# IrrigationSystemShield.net
KiCad netlist of a schematic drawn in EAGLE
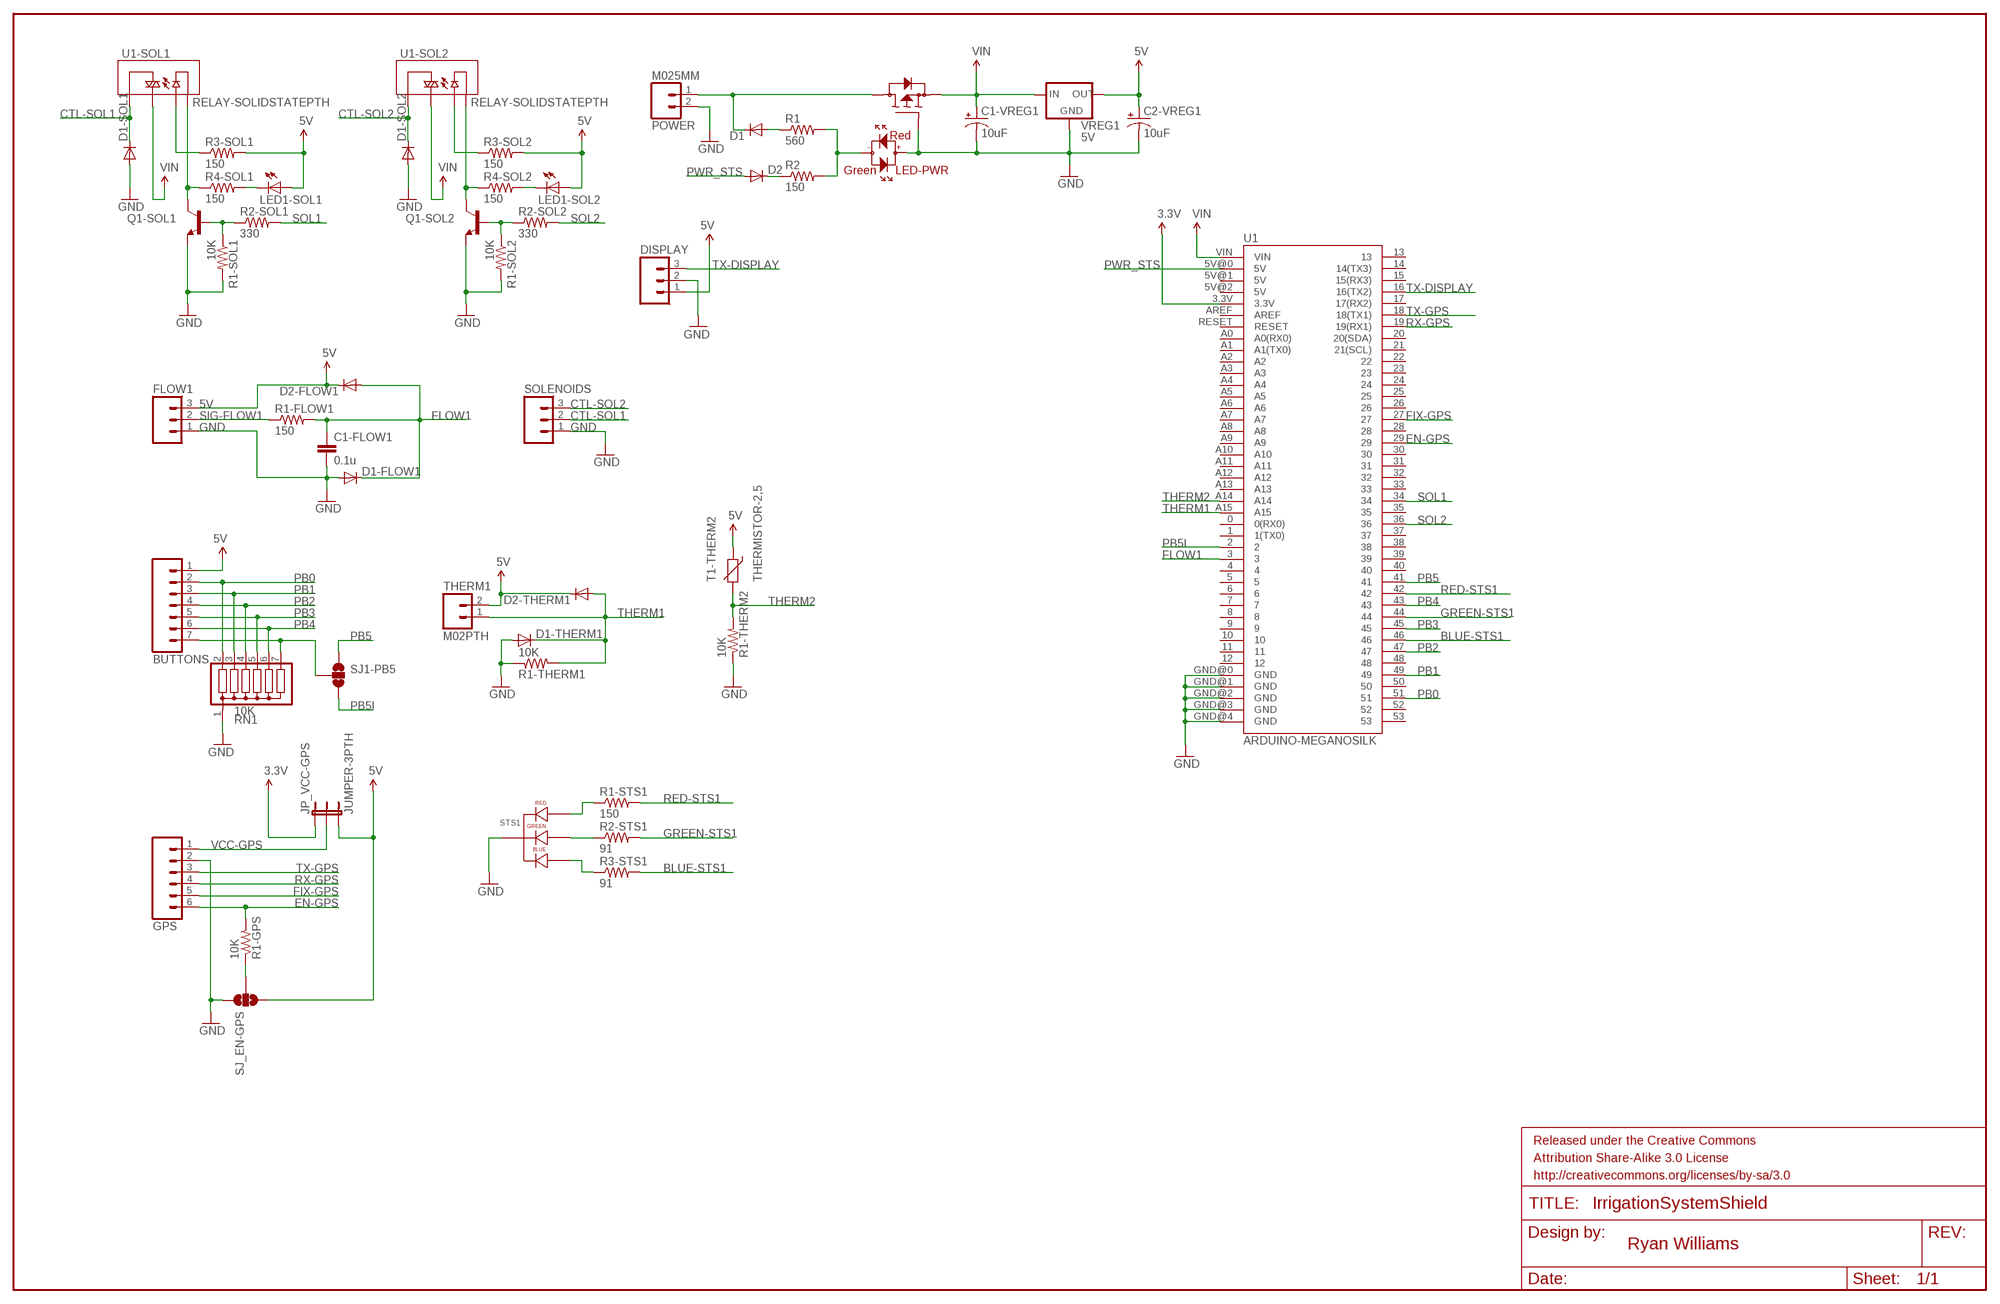
[diagram p0: schematic, sheet 1]

(export (version "E")
  (design (tool "Eeschema 10.0.6"))
  (components
    (comp (ref "BUTTONS")
      (value "M07")
      (footprint "eagle-import:1X07")
      (libsource (lib "eagle-import") (part "M07"))
    )
    (comp (ref "C1-FLOW1")
      (value "0.1u")
      (footprint "eagle-import:CAP-PTH-5MM")
      (libsource (lib "eagle-import") (part "CAPPTH1"))
    )
    (comp (ref "C1-VREG1")
      (value "10uF")
      (footprint "eagle-import:CPOL-RADIAL-10UF-25V")
      (libsource (lib "eagle-import") (part "10UF-25V-20%(PTH)"))
    )
    (comp (ref "C2-VREG1")
      (value "10uF")
      (footprint "eagle-import:CPOL-RADIAL-10UF-25V")
      (libsource (lib "eagle-import") (part "10UF-25V-20%(PTH)"))
    )
    (comp (ref "D1")
      (value "DIODEPTH")
      (footprint "eagle-import:DIODE-1N4001")
      (libsource (lib "eagle-import") (part "DIODEPTH"))
    )
    (comp (ref "D1-FLOW1")
      (value "DIODE1N4148")
      (footprint "eagle-import:DIODE-1N4148")
      (libsource (lib "eagle-import") (part "DIODE1N4148"))
    )
    (comp (ref "D1-SOL1")
      (value "DIODEPTH")
      (footprint "eagle-import:DIODE-1N4001")
      (libsource (lib "eagle-import") (part "DIODEPTH"))
    )
    (comp (ref "D1-SOL2")
      (value "DIODEPTH")
      (footprint "eagle-import:DIODE-1N4001")
      (libsource (lib "eagle-import") (part "DIODEPTH"))
    )
    (comp (ref "D1-THERM1")
      (value "DIODE1N4148")
      (footprint "eagle-import:DIODE-1N4148")
      (libsource (lib "eagle-import") (part "DIODE1N4148"))
    )
    (comp (ref "D2")
      (value "DIODEPTH")
      (footprint "eagle-import:DIODE-1N4001")
      (libsource (lib "eagle-import") (part "DIODEPTH"))
    )
    (comp (ref "D2-FLOW1")
      (value "DIODE1N4148")
      (footprint "eagle-import:DIODE-1N4148")
      (libsource (lib "eagle-import") (part "DIODE1N4148"))
    )
    (comp (ref "D2-THERM1")
      (value "DIODE1N4148")
      (footprint "eagle-import:DIODE-1N4148")
      (libsource (lib "eagle-import") (part "DIODE1N4148"))
    )
    (comp (ref "DISPLAY")
      (value "M03JST-PTH")
      (footprint "eagle-import:JST-3-PTH")
      (libsource (lib "eagle-import") (part "M03JST-PTH"))
    )
    (comp (ref "FET-1")
      (value "P-FET")
      (footprint "eagle-import:FQP27P06")
      (libsource (lib "eagle-import") (part "P-FET"))
    )
    (comp (ref "FLOW1")
      (value "M03-SCREW-5MM")
      (footprint "eagle-import:SCREWTERMINAL-5MM-3")
      (libsource (lib "eagle-import") (part "M03-SCREW-5MM"))
    )
    (comp (ref "FRAME1")
      (value "FRAME-LEDGER")
      (footprint "eagle-import:CREATIVE_COMMONS")
      (libsource (lib "eagle-import") (part "FRAME-LEDGER"))
    )
    (comp (ref "GPS")
      (value "M06SIP")
      (footprint "eagle-import:1X06")
      (libsource (lib "eagle-import") (part "M06SIP"))
    )
    (comp (ref "JP_VCC-GPS")
      (value "JUMPER-3PTH")
      (footprint "eagle-import:1X03")
      (libsource (lib "eagle-import") (part "JUMPER-3PTH"))
    )
    (comp (ref "LED-PWR")
      (value "LED-BIPOLARHGL*3362")
      (footprint "eagle-import:LED-5MM")
      (libsource (lib "eagle-import") (part "LED-BIPOLARL3362HG"))
    )
    (comp (ref "LED1-SOL1")
      (value "LED5MM")
      (footprint "eagle-import:LED5MM")
      (libsource (lib "eagle-import") (part "LED5MM"))
    )
    (comp (ref "LED1-SOL2")
      (value "LED5MM")
      (footprint "eagle-import:LED5MM")
      (libsource (lib "eagle-import") (part "LED5MM"))
    )
    (comp (ref "POWER")
      (value "M025MM")
      (footprint "eagle-import:SCREWTERMINAL-5MM-2")
      (libsource (lib "eagle-import") (part "M025MM"))
    )
    (comp (ref "Q1-SOL1")
      (value "TRANSISTOR_NPNTO92")
      (footprint "eagle-import:TO-92")
      (libsource (lib "eagle-import") (part "TRANSISTOR_NPNTO92"))
    )
    (comp (ref "Q1-SOL2")
      (value "TRANSISTOR_NPNTO92")
      (footprint "eagle-import:TO-92")
      (libsource (lib "eagle-import") (part "TRANSISTOR_NPNTO92"))
    )
    (comp (ref "R1")
      (value "560")
      (footprint "eagle-import:AXIAL-0.5")
      (libsource (lib "eagle-import") (part "RESISTORPTH-1/2W"))
    )
    (comp (ref "R1-FLOW1")
      (value "150")
      (footprint "eagle-import:AXIAL-0.4")
      (libsource (lib "eagle-import") (part "RESISTORPTH-1/4W"))
    )
    (comp (ref "R1-GPS")
      (value "10K")
      (footprint "eagle-import:AXIAL-0.4")
      (libsource (lib "eagle-import") (part "RESISTORPTH-1/4W"))
    )
    (comp (ref "R1-SOL1")
      (value "10K")
      (footprint "eagle-import:AXIAL-0.4")
      (libsource (lib "eagle-import") (part "RESISTORPTH-1/4W"))
    )
    (comp (ref "R1-SOL2")
      (value "10K")
      (footprint "eagle-import:AXIAL-0.4")
      (libsource (lib "eagle-import") (part "RESISTORPTH-1/4W"))
    )
    (comp (ref "R1-STS1")
      (value "150")
      (footprint "eagle-import:AXIAL-0.4")
      (libsource (lib "eagle-import") (part "RESISTORPTH-1/4W"))
    )
    (comp (ref "R1-THERM1")
      (value "10K")
      (footprint "eagle-import:AXIAL-0.4")
      (libsource (lib "eagle-import") (part "RESISTORPTH-1/4W"))
    )
    (comp (ref "R1-THERM2")
      (value "10K")
      (footprint "eagle-import:AXIAL-0.4")
      (libsource (lib "eagle-import") (part "RESISTORPTH-1/4W"))
    )
    (comp (ref "R2")
      (value "150")
      (footprint "eagle-import:AXIAL-0.4")
      (libsource (lib "eagle-import") (part "RESISTORPTH-1/4W"))
    )
    (comp (ref "R2-SOL1")
      (value "330")
      (footprint "eagle-import:AXIAL-0.4")
      (libsource (lib "eagle-import") (part "RESISTORPTH-1/4W"))
    )
    (comp (ref "R2-SOL2")
      (value "330")
      (footprint "eagle-import:AXIAL-0.4")
      (libsource (lib "eagle-import") (part "RESISTORPTH-1/4W"))
    )
    (comp (ref "R2-STS1")
      (value "91")
      (footprint "eagle-import:AXIAL-0.4")
      (libsource (lib "eagle-import") (part "RESISTORPTH-1/4W"))
    )
    (comp (ref "R3-SOL1")
      (value "150")
      (footprint "eagle-import:AXIAL-0.4")
      (libsource (lib "eagle-import") (part "RESISTORPTH-1/4W"))
    )
    (comp (ref "R3-SOL2")
      (value "150")
      (footprint "eagle-import:AXIAL-0.4")
      (libsource (lib "eagle-import") (part "RESISTORPTH-1/4W"))
    )
    (comp (ref "R3-STS1")
      (value "91")
      (footprint "eagle-import:AXIAL-0.4")
      (libsource (lib "eagle-import") (part "RESISTORPTH-1/4W"))
    )
    (comp (ref "R4-SOL1")
      (value "150")
      (footprint "eagle-import:AXIAL-0.4")
      (libsource (lib "eagle-import") (part "RESISTORPTH-1/4W"))
    )
    (comp (ref "R4-SOL2")
      (value "150")
      (footprint "eagle-import:AXIAL-0.4")
      (libsource (lib "eagle-import") (part "RESISTORPTH-1/4W"))
    )
    (comp (ref "RN1")
      (value "10K")
      (footprint "eagle-import:SIL7")
      (libsource (lib "eagle-import") (part "G06R"))
    )
    (comp (ref "SJ1-PB5")
      (value "SOLDERJUMPER_2WAYS")
      (footprint "eagle-import:SJ_3")
      (libsource (lib "eagle-import") (part "SOLDERJUMPER_2WAYS"))
    )
    (comp (ref "SJ_EN-GPS")
      (value "SOLDERJUMPER_2WAYS")
      (footprint "eagle-import:SJ_3")
      (libsource (lib "eagle-import") (part "SOLDERJUMPER_2WAYS"))
    )
    (comp (ref "SOLENOIDS")
      (value "M03-SCREW-5MM")
      (footprint "eagle-import:SCREWTERMINAL-5MM-3")
      (libsource (lib "eagle-import") (part "M03-SCREW-5MM"))
    )
    (comp (ref "STS1")
      (value "LED-RGB-CC-THRUDIFFUSE")
      (footprint "eagle-import:LED-RGB-THRU")
      (libsource (lib "eagle-import") (part "LED-RGB-CC-THRUDIFFUSE"))
    )
    (comp (ref "T1-THERM2")
      (value "THERMISTOR-2,5")
      (footprint "eagle-import:RS-2,5")
      (libsource (lib "eagle-import") (part "THERMISTOR-2,5"))
    )
    (comp (ref "THERM1")
      (value "M02PTH")
      (footprint "eagle-import:1X02")
      (libsource (lib "eagle-import") (part "M02PTH"))
    )
    (comp (ref "U1")
      (value "ARDUINO-MEGANOSILK")
      (footprint "eagle-import:ARDUINO_MEGA_NOSILK")
      (libsource (lib "eagle-import") (part "ARDUINO-MEGANOSILK"))
    )
    (comp (ref "U1-SOL1")
      (value "RELAY-SOLIDSTATEPTH")
      (footprint "eagle-import:RELAY-S108T02")
      (libsource (lib "eagle-import") (part "RELAY-SOLIDSTATEPTH"))
    )
    (comp (ref "U1-SOL2")
      (value "RELAY-SOLIDSTATEPTH")
      (footprint "eagle-import:RELAY-S108T02")
      (libsource (lib "eagle-import") (part "RELAY-SOLIDSTATEPTH"))
    )
    (comp (ref "VREG1")
      (value "5V")
      (footprint "eagle-import:TO220-IGO")
      (libsource (lib "eagle-import") (part "V_REG_78XXSINK"))
    )
  )
  (nets
    (net (code "1") (name "/BLUE-STS1") (class "Default")
      (node (ref "R3-STS1") (pin "P$2") (pinfunction "2_P$2") (pintype "passive"))
      (node (ref "U1") (pin "46") (pinfunction "46_46") (pintype "bidirectional"))
    )
    (net (code "2") (name "/CTL-SOL1") (class "Default")
      (node (ref "D1-SOL1") (pin "C") (pinfunction "C_C") (pintype "passive"))
      (node (ref "SOLENOIDS") (pin "2") (pinfunction "2_2") (pintype "passive"))
      (node (ref "U1-SOL1") (pin "1") (pinfunction "T1_1") (pintype "bidirectional"))
    )
    (net (code "3") (name "/CTL-SOL2") (class "Default")
      (node (ref "D1-SOL2") (pin "C") (pinfunction "C_C") (pintype "passive"))
      (node (ref "SOLENOIDS") (pin "3") (pinfunction "3_3") (pintype "passive"))
      (node (ref "U1-SOL2") (pin "1") (pinfunction "T1_1") (pintype "bidirectional"))
    )
    (net (code "4") (name "/EN-GPS") (class "Default")
      (node (ref "GPS") (pin "6") (pinfunction "6_6") (pintype "passive"))
      (node (ref "R1-GPS") (pin "P$2") (pinfunction "2_P$2") (pintype "passive"))
      (node (ref "U1") (pin "29") (pinfunction "29_29") (pintype "bidirectional"))
    )
    (net (code "5") (name "/FIX-GPS") (class "Default")
      (node (ref "GPS") (pin "5") (pinfunction "5_5") (pintype "passive"))
      (node (ref "U1") (pin "27") (pinfunction "27_27") (pintype "bidirectional"))
    )
    (net (code "6") (name "/FLOW1") (class "Default")
      (node (ref "C1-FLOW1") (pin "1") (pinfunction "1_1") (pintype "passive"))
      (node (ref "D1-FLOW1") (pin "C") (pinfunction "C_C") (pintype "passive"))
      (node (ref "D2-FLOW1") (pin "A") (pinfunction "A_A") (pintype "passive"))
      (node (ref "R1-FLOW1") (pin "P$2") (pinfunction "2_P$2") (pintype "passive"))
      (node (ref "U1") (pin "3") (pinfunction "3_3") (pintype "bidirectional"))
    )
    (net (code "7") (name "/GREEN-STS1") (class "Default")
      (node (ref "R2-STS1") (pin "P$2") (pinfunction "2_P$2") (pintype "passive"))
      (node (ref "U1") (pin "44") (pinfunction "44_44") (pintype "bidirectional"))
    )
    (net (code "8") (name "/PB0") (class "Default")
      (node (ref "BUTTONS") (pin "2") (pinfunction "2_2") (pintype "passive"))
      (node (ref "RN1") (pin "2") (pinfunction "2_2") (pintype "passive"))
      (node (ref "U1") (pin "51") (pinfunction "51_51") (pintype "bidirectional"))
    )
    (net (code "9") (name "/PB1") (class "Default")
      (node (ref "BUTTONS") (pin "3") (pinfunction "3_3") (pintype "passive"))
      (node (ref "RN1") (pin "3") (pinfunction "3_3") (pintype "passive"))
      (node (ref "U1") (pin "49") (pinfunction "49_49") (pintype "bidirectional"))
    )
    (net (code "10") (name "/PB2") (class "Default")
      (node (ref "BUTTONS") (pin "4") (pinfunction "4_4") (pintype "passive"))
      (node (ref "RN1") (pin "4") (pinfunction "4_4") (pintype "passive"))
      (node (ref "U1") (pin "47") (pinfunction "47_47") (pintype "bidirectional"))
    )
    (net (code "11") (name "/PB3") (class "Default")
      (node (ref "BUTTONS") (pin "5") (pinfunction "5_5") (pintype "passive"))
      (node (ref "RN1") (pin "5") (pinfunction "5_5") (pintype "passive"))
      (node (ref "U1") (pin "45") (pinfunction "45_45") (pintype "bidirectional"))
    )
    (net (code "12") (name "/PB4") (class "Default")
      (node (ref "BUTTONS") (pin "6") (pinfunction "6_6") (pintype "passive"))
      (node (ref "RN1") (pin "6") (pinfunction "6_6") (pintype "passive"))
      (node (ref "U1") (pin "43") (pinfunction "43_43") (pintype "bidirectional"))
    )
    (net (code "13") (name "/PB5") (class "Default")
      (node (ref "SJ1-PB5") (pin "1") (pinfunction "1_1") (pintype "passive"))
      (node (ref "U1") (pin "41") (pinfunction "41_41") (pintype "bidirectional"))
    )
    (net (code "14") (name "/PB5I") (class "Default")
      (node (ref "SJ1-PB5") (pin "3") (pinfunction "3_3") (pintype "passive"))
      (node (ref "U1") (pin "2") (pinfunction "2_2") (pintype "bidirectional"))
    )
    (net (code "15") (name "/PWR_STS") (class "Default")
      (node (ref "D2") (pin "A") (pinfunction "A_A") (pintype "passive"))
      (node (ref "U1") (pin "5V@0") (pinfunction "5V_5V@0") (pintype "bidirectional"))
    )
    (net (code "16") (name "/RED-STS1") (class "Default")
      (node (ref "R1-STS1") (pin "P$2") (pinfunction "2_P$2") (pintype "passive"))
      (node (ref "U1") (pin "42") (pinfunction "42_42") (pintype "bidirectional"))
    )
    (net (code "17") (name "/RX-GPS") (class "Default")
      (node (ref "GPS") (pin "4") (pinfunction "4_4") (pintype "passive"))
      (node (ref "U1") (pin "19") (pinfunction "19(RX1)_19") (pintype "bidirectional"))
    )
    (net (code "18") (name "/SIG-FLOW1") (class "Default")
      (node (ref "FLOW1") (pin "2") (pinfunction "2_2") (pintype "passive"))
      (node (ref "R1-FLOW1") (pin "P$1") (pinfunction "1_P$1") (pintype "passive"))
    )
    (net (code "19") (name "/SOL1") (class "Default")
      (node (ref "R2-SOL1") (pin "P$2") (pinfunction "2_P$2") (pintype "passive"))
      (node (ref "U1") (pin "34") (pinfunction "34_34") (pintype "bidirectional"))
    )
    (net (code "20") (name "/SOL2") (class "Default")
      (node (ref "R2-SOL2") (pin "P$2") (pinfunction "2_P$2") (pintype "passive"))
      (node (ref "U1") (pin "36") (pinfunction "36_36") (pintype "bidirectional"))
    )
    (net (code "21") (name "/THERM1") (class "Default")
      (node (ref "D1-THERM1") (pin "C") (pinfunction "C_C") (pintype "passive"))
      (node (ref "D2-THERM1") (pin "A") (pinfunction "A_A") (pintype "passive"))
      (node (ref "R1-THERM1") (pin "P$2") (pinfunction "2_P$2") (pintype "passive"))
      (node (ref "THERM1") (pin "1") (pinfunction "1_1") (pintype "passive"))
      (node (ref "U1") (pin "A15") (pinfunction "A15_A15") (pintype "bidirectional"))
    )
    (net (code "22") (name "/THERM2") (class "Default")
      (node (ref "R1-THERM2") (pin "P$2") (pinfunction "2_P$2") (pintype "passive"))
      (node (ref "T1-THERM2") (pin "2") (pinfunction "2_2") (pintype "passive"))
      (node (ref "U1") (pin "A14") (pinfunction "A14_A14") (pintype "bidirectional"))
    )
    (net (code "23") (name "/TX-DISPLAY") (class "Default")
      (node (ref "DISPLAY") (pin "3") (pinfunction "3_3") (pintype "passive"))
      (node (ref "U1") (pin "16") (pinfunction "16(TX2)_16") (pintype "bidirectional"))
    )
    (net (code "24") (name "/TX-GPS") (class "Default")
      (node (ref "GPS") (pin "3") (pinfunction "3_3") (pintype "passive"))
      (node (ref "U1") (pin "18") (pinfunction "18(TX1)_18") (pintype "bidirectional"))
    )
    (net (code "25") (name "/VCC-GPS") (class "Default")
      (node (ref "GPS") (pin "1") (pinfunction "1_1") (pintype "passive"))
      (node (ref "JP_VCC-GPS") (pin "2") (pinfunction "2_2") (pintype "passive"))
    )
    (net (code "26") (name "3.3V") (class "Default")
      (node (ref "JP_VCC-GPS") (pin "1") (pinfunction "1_1") (pintype "passive"))
      (node (ref "U1") (pin "3.3V") (pinfunction "3.3V_3.3V") (pintype "bidirectional"))
    )
    (net (code "27") (name "5V") (class "Default")
      (node (ref "BUTTONS") (pin "1") (pinfunction "1_1") (pintype "passive"))
      (node (ref "C2-VREG1") (pin "1") (pinfunction "+_1") (pintype "passive"))
      (node (ref "D2-FLOW1") (pin "C") (pinfunction "C_C") (pintype "passive"))
      (node (ref "D2-THERM1") (pin "C") (pinfunction "C_C") (pintype "passive"))
      (node (ref "DISPLAY") (pin "1") (pinfunction "1_1") (pintype "passive"))
      (node (ref "FLOW1") (pin "3") (pinfunction "3_3") (pintype "passive"))
      (node (ref "JP_VCC-GPS") (pin "3") (pinfunction "3_3") (pintype "passive"))
      (node (ref "LED1-SOL1") (pin "A") (pinfunction "A_A") (pintype "passive"))
      (node (ref "LED1-SOL2") (pin "A") (pinfunction "A_A") (pintype "passive"))
      (node (ref "R3-SOL1") (pin "P$2") (pinfunction "2_P$2") (pintype "passive"))
      (node (ref "R3-SOL2") (pin "P$2") (pinfunction "2_P$2") (pintype "passive"))
      (node (ref "SJ_EN-GPS") (pin "3") (pinfunction "3_3") (pintype "passive"))
      (node (ref "T1-THERM2") (pin "1") (pinfunction "1_1") (pintype "passive"))
      (node (ref "THERM1") (pin "2") (pinfunction "2_2") (pintype "passive"))
      (node (ref "VREG1") (pin "OUT") (pinfunction "OUT_OUT") (pintype "output"))
    )
    (net (code "28") (name "GND") (class "Default")
      (node (ref "C1-FLOW1") (pin "2") (pinfunction "2_2") (pintype "passive"))
      (node (ref "C1-VREG1") (pin "2") (pinfunction "-_2") (pintype "passive"))
      (node (ref "C2-VREG1") (pin "2") (pinfunction "-_2") (pintype "passive"))
      (node (ref "D1-FLOW1") (pin "A") (pinfunction "A_A") (pintype "passive"))
      (node (ref "D1-SOL1") (pin "A") (pinfunction "A_A") (pintype "passive"))
      (node (ref "D1-SOL2") (pin "A") (pinfunction "A_A") (pintype "passive"))
      (node (ref "D1-THERM1") (pin "A") (pinfunction "A_A") (pintype "passive"))
      (node (ref "DISPLAY") (pin "2") (pinfunction "2_2") (pintype "passive"))
      (node (ref "FET-1") (pin "GATE") (pinfunction "GATE_GATE") (pintype "bidirectional"))
      (node (ref "FLOW1") (pin "1") (pinfunction "1_1") (pintype "passive"))
      (node (ref "GPS") (pin "2") (pinfunction "2_2") (pintype "passive"))
      (node (ref "LED-PWR") (pin "ANODE") (pinfunction "ANODE_ANODE") (pintype "bidirectional"))
      (node (ref "POWER") (pin "2") (pinfunction "2_2") (pintype "passive"))
      (node (ref "Q1-SOL1") (pin "1") (pinfunction "E_1") (pintype "passive"))
      (node (ref "Q1-SOL2") (pin "1") (pinfunction "E_1") (pintype "passive"))
      (node (ref "R1-SOL1") (pin "P$2") (pinfunction "2_P$2") (pintype "passive"))
      (node (ref "R1-SOL2") (pin "P$2") (pinfunction "2_P$2") (pintype "passive"))
      (node (ref "R1-THERM1") (pin "P$1") (pinfunction "1_P$1") (pintype "passive"))
      (node (ref "R1-THERM2") (pin "P$1") (pinfunction "1_P$1") (pintype "passive"))
      (node (ref "RN1") (pin "1") (pinfunction "1_1") (pintype "passive"))
      (node (ref "SJ_EN-GPS") (pin "1") (pinfunction "1_1") (pintype "passive"))
      (node (ref "SOLENOIDS") (pin "1") (pinfunction "1_1") (pintype "passive"))
      (node (ref "STS1") (pin "2") (pinfunction "CATHODE_2") (pintype "bidirectional"))
      (node (ref "U1") (pin "GND@0") (pinfunction "GND_GND@0") (pintype "bidirectional"))
      (node (ref "U1") (pin "GND@1") (pinfunction "GND_GND@1") (pintype "bidirectional"))
      (node (ref "U1") (pin "GND@2") (pinfunction "GND_GND@2") (pintype "bidirectional"))
      (node (ref "U1") (pin "GND@3") (pinfunction "GND_GND@3") (pintype "bidirectional"))
      (node (ref "U1") (pin "GND@4") (pinfunction "GND_GND@4") (pintype "bidirectional"))
      (node (ref "VREG1") (pin "GND") (pinfunction "GND_GND") (pintype "input"))
    )
    (net (code "29") (name "Net-(BUTTONS-Pad7)") (class "Default")
      (node (ref "BUTTONS") (pin "7") (pinfunction "7_7") (pintype "passive"))
      (node (ref "RN1") (pin "7") (pinfunction "7_7") (pintype "passive"))
      (node (ref "SJ1-PB5") (pin "2") (pinfunction "2_2") (pintype "passive"))
    )
    (net (code "30") (name "Net-(D1-PadC)") (class "Default")
      (node (ref "D1") (pin "C") (pinfunction "C_C") (pintype "passive"))
      (node (ref "FET-1") (pin "DRAIN") (pinfunction "DRAIN_DRAIN") (pintype "bidirectional"))
      (node (ref "POWER") (pin "1") (pinfunction "1_1") (pintype "passive"))
    )
    (net (code "31") (name "Net-(LED1-SOL1-C)") (class "Default")
      (node (ref "LED1-SOL1") (pin "K") (pinfunction "C_K") (pintype "passive"))
      (node (ref "R4-SOL1") (pin "P$2") (pinfunction "2_P$2") (pintype "passive"))
    )
    (net (code "32") (name "Net-(LED1-SOL2-C)") (class "Default")
      (node (ref "LED1-SOL2") (pin "K") (pinfunction "C_K") (pintype "passive"))
      (node (ref "R4-SOL2") (pin "P$2") (pinfunction "2_P$2") (pintype "passive"))
    )
    (net (code "33") (name "Net-(Q1-SOL1-B)") (class "Default")
      (node (ref "Q1-SOL1") (pin "2") (pinfunction "B_2") (pintype "passive"))
      (node (ref "R1-SOL1") (pin "P$1") (pinfunction "1_P$1") (pintype "passive"))
      (node (ref "R2-SOL1") (pin "P$1") (pinfunction "1_P$1") (pintype "passive"))
    )
    (net (code "34") (name "Net-(Q1-SOL1-C)") (class "Default")
      (node (ref "Q1-SOL1") (pin "3") (pinfunction "C_3") (pintype "passive"))
      (node (ref "R4-SOL1") (pin "P$1") (pinfunction "1_P$1") (pintype "passive"))
      (node (ref "U1-SOL1") (pin "4") (pinfunction "-_4") (pintype "bidirectional"))
    )
    (net (code "35") (name "Net-(Q1-SOL2-B)") (class "Default")
      (node (ref "Q1-SOL2") (pin "2") (pinfunction "B_2") (pintype "passive"))
      (node (ref "R1-SOL2") (pin "P$1") (pinfunction "1_P$1") (pintype "passive"))
      (node (ref "R2-SOL2") (pin "P$1") (pinfunction "1_P$1") (pintype "passive"))
    )
    (net (code "36") (name "Net-(Q1-SOL2-C)") (class "Default")
      (node (ref "Q1-SOL2") (pin "3") (pinfunction "C_3") (pintype "passive"))
      (node (ref "R4-SOL2") (pin "P$1") (pinfunction "1_P$1") (pintype "passive"))
      (node (ref "U1-SOL2") (pin "4") (pinfunction "-_4") (pintype "bidirectional"))
    )
    (net (code "37") (name "Net-(R1-1)") (class "Default")
      (node (ref "D1") (pin "A") (pinfunction "A_A") (pintype "passive"))
      (node (ref "R1") (pin "P$1") (pinfunction "1_P$1") (pintype "passive"))
    )
    (net (code "38") (name "Net-(R1-2)") (class "Default")
      (node (ref "LED-PWR") (pin "CATHODE") (pinfunction "CATHODE_CATHODE") (pintype "bidirectional"))
      (node (ref "R1") (pin "P$2") (pinfunction "2_P$2") (pintype "passive"))
      (node (ref "R2") (pin "P$2") (pinfunction "2_P$2") (pintype "passive"))
    )
    (net (code "39") (name "Net-(R1-GPS-1)") (class "Default")
      (node (ref "R1-GPS") (pin "P$1") (pinfunction "1_P$1") (pintype "passive"))
      (node (ref "SJ_EN-GPS") (pin "2") (pinfunction "2_2") (pintype "passive"))
    )
    (net (code "40") (name "Net-(R1-STS1-1)") (class "Default")
      (node (ref "R1-STS1") (pin "P$1") (pinfunction "1_P$1") (pintype "passive"))
      (node (ref "STS1") (pin "1") (pinfunction "RED_CATHODE_1") (pintype "bidirectional"))
    )
    (net (code "41") (name "Net-(R2-1)") (class "Default")
      (node (ref "D2") (pin "C") (pinfunction "C_C") (pintype "passive"))
      (node (ref "R2") (pin "P$1") (pinfunction "1_P$1") (pintype "passive"))
    )
    (net (code "42") (name "Net-(R2-STS1-1)") (class "Default")
      (node (ref "R2-STS1") (pin "P$1") (pinfunction "1_P$1") (pintype "passive"))
      (node (ref "STS1") (pin "3") (pinfunction "GREEN_CATHODE_3") (pintype "bidirectional"))
    )
    (net (code "43") (name "Net-(R3-SOL1-1)") (class "Default")
      (node (ref "R3-SOL1") (pin "P$1") (pinfunction "1_P$1") (pintype "passive"))
      (node (ref "U1-SOL1") (pin "3") (pinfunction "+_3") (pintype "bidirectional"))
    )
    (net (code "44") (name "Net-(R3-SOL2-1)") (class "Default")
      (node (ref "R3-SOL2") (pin "P$1") (pinfunction "1_P$1") (pintype "passive"))
      (node (ref "U1-SOL2") (pin "3") (pinfunction "+_3") (pintype "bidirectional"))
    )
    (net (code "45") (name "Net-(R3-STS1-1)") (class "Default")
      (node (ref "R3-STS1") (pin "P$1") (pinfunction "1_P$1") (pintype "passive"))
      (node (ref "STS1") (pin "4") (pinfunction "BLUE_CATHODE_4") (pintype "bidirectional"))
    )
    (net (code "46") (name "VIN") (class "Default")
      (node (ref "C1-VREG1") (pin "1") (pinfunction "+_1") (pintype "passive"))
      (node (ref "FET-1") (pin "SOURCE") (pinfunction "SOURCE_SOURCE") (pintype "bidirectional"))
      (node (ref "U1") (pin "VIN") (pinfunction "VIN_VIN") (pintype "bidirectional"))
      (node (ref "U1-SOL1") (pin "2") (pinfunction "T2_2") (pintype "bidirectional"))
      (node (ref "U1-SOL2") (pin "2") (pinfunction "T2_2") (pintype "bidirectional"))
      (node (ref "VREG1") (pin "IN") (pinfunction "IN_IN") (pintype "input"))
    )
    (net (code "47") (name "unconnected-(U1-0(RX0)-Pad0)") (class "Default")
      (node (ref "U1") (pin "0") (pinfunction "0(RX0)_0") (pintype "bidirectional"))
    )
    (net (code "48") (name "unconnected-(U1-1(TX0)-Pad1)") (class "Default")
      (node (ref "U1") (pin "1") (pinfunction "1(TX0)_1") (pintype "bidirectional"))
    )
    (net (code "49") (name "unconnected-(U1-5V-Pad5V@1)") (class "Default")
      (node (ref "U1") (pin "5V@1") (pinfunction "5V_5V@1") (pintype "bidirectional"))
    )
    (net (code "50") (name "unconnected-(U1-5V-Pad5V@2)") (class "Default")
      (node (ref "U1") (pin "5V@2") (pinfunction "5V_5V@2") (pintype "bidirectional"))
    )
    (net (code "51") (name "unconnected-(U1-14(TX3)-Pad14)") (class "Default")
      (node (ref "U1") (pin "14") (pinfunction "14(TX3)_14") (pintype "bidirectional"))
    )
    (net (code "52") (name "unconnected-(U1-15(RX3)-Pad15)") (class "Default")
      (node (ref "U1") (pin "15") (pinfunction "15(RX3)_15") (pintype "bidirectional"))
    )
    (net (code "53") (name "unconnected-(U1-17(RX2)-Pad17)") (class "Default")
      (node (ref "U1") (pin "17") (pinfunction "17(RX2)_17") (pintype "bidirectional"))
    )
    (net (code "54") (name "unconnected-(U1-20(SDA)-Pad20)") (class "Default")
      (node (ref "U1") (pin "20") (pinfunction "20(SDA)_20") (pintype "bidirectional"))
    )
    (net (code "55") (name "unconnected-(U1-21(SCL)-Pad21)") (class "Default")
      (node (ref "U1") (pin "21") (pinfunction "21(SCL)_21") (pintype "bidirectional"))
    )
    (net (code "56") (name "unconnected-(U1-A0(RX0)-PadA0)") (class "Default")
      (node (ref "U1") (pin "A0") (pinfunction "A0(RX0)_A0") (pintype "bidirectional"))
    )
    (net (code "57") (name "unconnected-(U1-A1(TX0)-PadA1)") (class "Default")
      (node (ref "U1") (pin "A1") (pinfunction "A1(TX0)_A1") (pintype "bidirectional"))
    )
    (net (code "58") (name "unconnected-(U1-Pad4)") (class "Default")
      (node (ref "U1") (pin "4") (pinfunction "4_4") (pintype "bidirectional"))
    )
    (net (code "59") (name "unconnected-(U1-Pad5)") (class "Default")
      (node (ref "U1") (pin "5") (pinfunction "5_5") (pintype "bidirectional"))
    )
    (net (code "60") (name "unconnected-(U1-Pad6)") (class "Default")
      (node (ref "U1") (pin "6") (pinfunction "6_6") (pintype "bidirectional"))
    )
    (net (code "61") (name "unconnected-(U1-Pad7)") (class "Default")
      (node (ref "U1") (pin "7") (pinfunction "7_7") (pintype "bidirectional"))
    )
    (net (code "62") (name "unconnected-(U1-Pad8)") (class "Default")
      (node (ref "U1") (pin "8") (pinfunction "8_8") (pintype "bidirectional"))
    )
    (net (code "63") (name "unconnected-(U1-Pad9)") (class "Default")
      (node (ref "U1") (pin "9") (pinfunction "9_9") (pintype "bidirectional"))
    )
    (net (code "64") (name "unconnected-(U1-Pad10)") (class "Default")
      (node (ref "U1") (pin "10") (pinfunction "10_10") (pintype "bidirectional"))
    )
    (net (code "65") (name "unconnected-(U1-Pad11)") (class "Default")
      (node (ref "U1") (pin "11") (pinfunction "11_11") (pintype "bidirectional"))
    )
    (net (code "66") (name "unconnected-(U1-Pad12)") (class "Default")
      (node (ref "U1") (pin "12") (pinfunction "12_12") (pintype "bidirectional"))
    )
    (net (code "67") (name "unconnected-(U1-Pad13)") (class "Default")
      (node (ref "U1") (pin "13") (pinfunction "13_13") (pintype "bidirectional"))
    )
    (net (code "68") (name "unconnected-(U1-Pad22)") (class "Default")
      (node (ref "U1") (pin "22") (pinfunction "22_22") (pintype "bidirectional"))
    )
    (net (code "69") (name "unconnected-(U1-Pad23)") (class "Default")
      (node (ref "U1") (pin "23") (pinfunction "23_23") (pintype "bidirectional"))
    )
    (net (code "70") (name "unconnected-(U1-Pad24)") (class "Default")
      (node (ref "U1") (pin "24") (pinfunction "24_24") (pintype "bidirectional"))
    )
    (net (code "71") (name "unconnected-(U1-Pad25)") (class "Default")
      (node (ref "U1") (pin "25") (pinfunction "25_25") (pintype "bidirectional"))
    )
    (net (code "72") (name "unconnected-(U1-Pad26)") (class "Default")
      (node (ref "U1") (pin "26") (pinfunction "26_26") (pintype "bidirectional"))
    )
    (net (code "73") (name "unconnected-(U1-Pad28)") (class "Default")
      (node (ref "U1") (pin "28") (pinfunction "28_28") (pintype "bidirectional"))
    )
    (net (code "74") (name "unconnected-(U1-Pad30)") (class "Default")
      (node (ref "U1") (pin "30") (pinfunction "30_30") (pintype "bidirectional"))
    )
    (net (code "75") (name "unconnected-(U1-Pad31)") (class "Default")
      (node (ref "U1") (pin "31") (pinfunction "31_31") (pintype "bidirectional"))
    )
    (net (code "76") (name "unconnected-(U1-Pad32)") (class "Default")
      (node (ref "U1") (pin "32") (pinfunction "32_32") (pintype "bidirectional"))
    )
    (net (code "77") (name "unconnected-(U1-Pad33)") (class "Default")
      (node (ref "U1") (pin "33") (pinfunction "33_33") (pintype "bidirectional"))
    )
    (net (code "78") (name "unconnected-(U1-Pad35)") (class "Default")
      (node (ref "U1") (pin "35") (pinfunction "35_35") (pintype "bidirectional"))
    )
    (net (code "79") (name "unconnected-(U1-Pad37)") (class "Default")
      (node (ref "U1") (pin "37") (pinfunction "37_37") (pintype "bidirectional"))
    )
    (net (code "80") (name "unconnected-(U1-Pad38)") (class "Default")
      (node (ref "U1") (pin "38") (pinfunction "38_38") (pintype "bidirectional"))
    )
    (net (code "81") (name "unconnected-(U1-Pad39)") (class "Default")
      (node (ref "U1") (pin "39") (pinfunction "39_39") (pintype "bidirectional"))
    )
    (net (code "82") (name "unconnected-(U1-Pad40)") (class "Default")
      (node (ref "U1") (pin "40") (pinfunction "40_40") (pintype "bidirectional"))
    )
    (net (code "83") (name "unconnected-(U1-Pad48)") (class "Default")
      (node (ref "U1") (pin "48") (pinfunction "48_48") (pintype "bidirectional"))
    )
    (net (code "84") (name "unconnected-(U1-Pad50)") (class "Default")
      (node (ref "U1") (pin "50") (pinfunction "50_50") (pintype "bidirectional"))
    )
    (net (code "85") (name "unconnected-(U1-Pad52)") (class "Default")
      (node (ref "U1") (pin "52") (pinfunction "52_52") (pintype "bidirectional"))
    )
    (net (code "86") (name "unconnected-(U1-Pad53)") (class "Default")
      (node (ref "U1") (pin "53") (pinfunction "53_53") (pintype "bidirectional"))
    )
    (net (code "87") (name "unconnected-(U1-PadA2)") (class "Default")
      (node (ref "U1") (pin "A2") (pinfunction "A2_A2") (pintype "bidirectional"))
    )
    (net (code "88") (name "unconnected-(U1-PadA3)") (class "Default")
      (node (ref "U1") (pin "A3") (pinfunction "A3_A3") (pintype "bidirectional"))
    )
    (net (code "89") (name "unconnected-(U1-PadA4)") (class "Default")
      (node (ref "U1") (pin "A4") (pinfunction "A4_A4") (pintype "bidirectional"))
    )
    (net (code "90") (name "unconnected-(U1-PadA5)") (class "Default")
      (node (ref "U1") (pin "A5") (pinfunction "A5_A5") (pintype "bidirectional"))
    )
    (net (code "91") (name "unconnected-(U1-PadA6)") (class "Default")
      (node (ref "U1") (pin "A6") (pinfunction "A6_A6") (pintype "bidirectional"))
    )
    (net (code "92") (name "unconnected-(U1-PadA7)") (class "Default")
      (node (ref "U1") (pin "A7") (pinfunction "A7_A7") (pintype "bidirectional"))
    )
    (net (code "93") (name "unconnected-(U1-PadA8)") (class "Default")
      (node (ref "U1") (pin "A8") (pinfunction "A8_A8") (pintype "bidirectional"))
    )
    (net (code "94") (name "unconnected-(U1-PadA9)") (class "Default")
      (node (ref "U1") (pin "A9") (pinfunction "A9_A9") (pintype "bidirectional"))
    )
    (net (code "95") (name "unconnected-(U1-PadA10)") (class "Default")
      (node (ref "U1") (pin "A10") (pinfunction "A10_A10") (pintype "bidirectional"))
    )
    (net (code "96") (name "unconnected-(U1-PadA11)") (class "Default")
      (node (ref "U1") (pin "A11") (pinfunction "A11_A11") (pintype "bidirectional"))
    )
    (net (code "97") (name "unconnected-(U1-PadA12)") (class "Default")
      (node (ref "U1") (pin "A12") (pinfunction "A12_A12") (pintype "bidirectional"))
    )
    (net (code "98") (name "unconnected-(U1-PadA13)") (class "Default")
      (node (ref "U1") (pin "A13") (pinfunction "A13_A13") (pintype "bidirectional"))
    )
    (net (code "99") (name "unconnected-(U1-PadAREF)") (class "Default")
      (node (ref "U1") (pin "AREF") (pinfunction "AREF_AREF") (pintype "bidirectional"))
    )
    (net (code "100") (name "unconnected-(U1-PadRESET)") (class "Default")
      (node (ref "U1") (pin "RESET") (pinfunction "RESET_RESET") (pintype "bidirectional"))
    )
  )
)
